# 1pil-2motor-1back.net
KiCad netlist of a schematic drawn in EAGLE
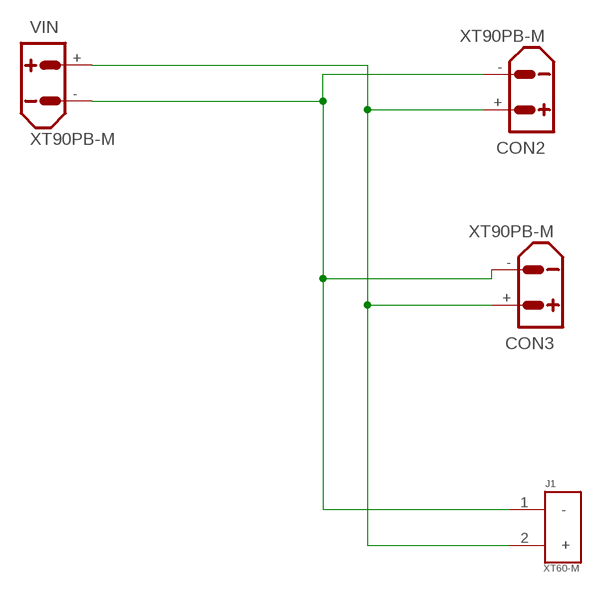
[diagram p0: schematic, sheet 1]

(export (version "E")
  (design (tool "Eeschema 10.0.6"))
  (components
    (comp (ref "CON2")
      (value "XT90PB-M")
      (footprint "eagle-import:XT90PB-M")
      (libsource (lib "eagle-import") (part "XT90PB-M"))
    )
    (comp (ref "CON3")
      (value "XT90PB-M")
      (footprint "eagle-import:XT90PB-M")
      (libsource (lib "eagle-import") (part "XT90PB-M"))
    )
    (comp (ref "J1")
      (value "XT60-M")
      (footprint "eagle-import:AMASS_XT60-M")
      (fields (field (name "MF") "AMASS"))
      (libsource (lib "eagle-import") (part "XT60-M"))
    )
    (comp (ref "VIN")
      (value "XT90PB-M")
      (footprint "eagle-import:XT90PB-M")
      (libsource (lib "eagle-import") (part "XT90PB-M"))
    )
  )
  (nets
    (net (code "1") (name "Net-(J1-+)") (class "Default")
      (node (ref "CON2") (pin "+") (pinfunction "+_+") (pintype "power_in"))
      (node (ref "CON3") (pin "+") (pinfunction "+_+") (pintype "power_in"))
      (node (ref "J1") (pin "2") (pinfunction "+_2") (pintype "passive"))
      (node (ref "VIN") (pin "+") (pinfunction "+_+") (pintype "power_in"))
    )
    (net (code "2") (name "Net-(J1--)") (class "Default")
      (node (ref "CON2") (pin "-") (pinfunction "-_-") (pintype "power_in"))
      (node (ref "CON3") (pin "-") (pinfunction "-_-") (pintype "power_in"))
      (node (ref "J1") (pin "1") (pinfunction "-_1") (pintype "passive"))
      (node (ref "VIN") (pin "-") (pinfunction "-_-") (pintype "power_in"))
    )
  )
)
